# Sheet2.net
KiCad netlist of a schematic drawn in Altium Designer
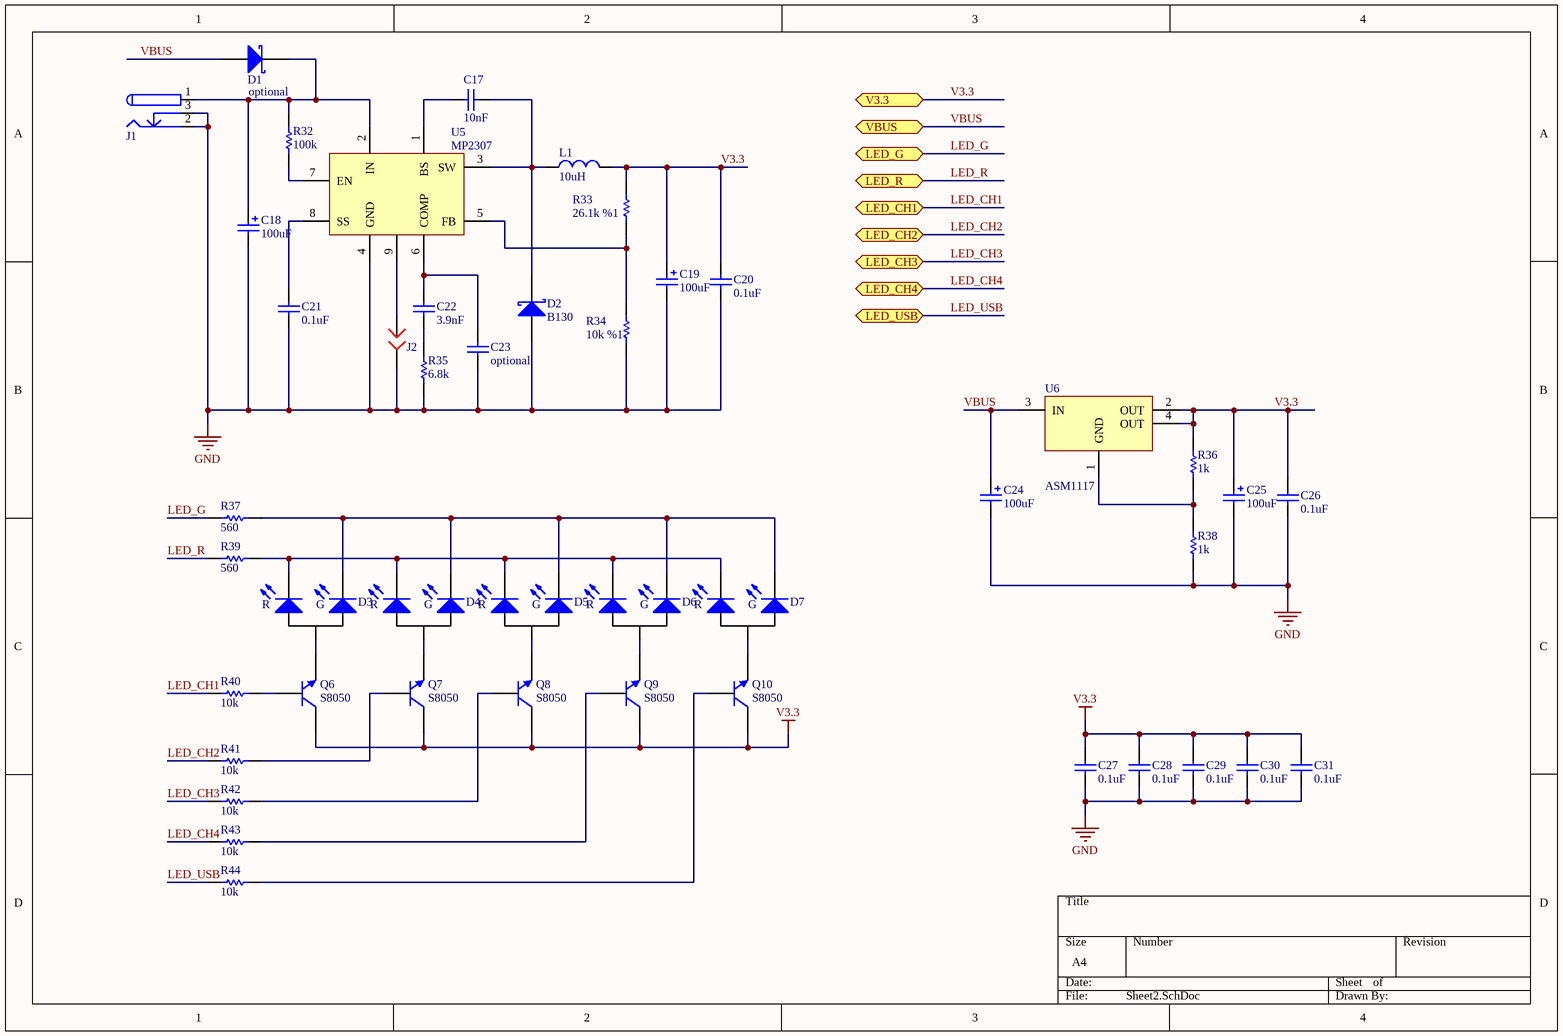
[diagram p0: Sheet2.SchDoc]

(export (version "E")
  (design (tool "Eeschema 10.0.6"))
  (components
    (comp (ref "C17")
      (value "10nF")
      (footprint "0805")
      (fields (field (name "Comment") "Cap"))
      (libsource (lib "SelfLib") (part "Cap"))
    )
    (comp (ref "C18")
      (value "100uF")
      (footprint "1206A")
      (fields (field (name "Comment") "Cap"))
      (libsource (lib "SelfLib") (part "Cap Pol"))
    )
    (comp (ref "C19")
      (value "100uF")
      (footprint "1206A")
      (fields (field (name "Comment") "Cap"))
      (libsource (lib "SelfLib") (part "Cap Pol"))
    )
    (comp (ref "C20")
      (value "0.1uF")
      (footprint "0805")
      (fields (field (name "Comment") "Cap"))
      (libsource (lib "SelfLib") (part "Cap"))
    )
    (comp (ref "C21")
      (value "0.1uF")
      (footprint "0805")
      (fields (field (name "Comment") "Cap"))
      (libsource (lib "SelfLib") (part "Cap"))
    )
    (comp (ref "C22")
      (value "3.9nF")
      (footprint "0805")
      (fields (field (name "Comment") "Cap"))
      (libsource (lib "SelfLib") (part "Cap"))
    )
    (comp (ref "C23")
      (value "optional")
      (footprint "0805")
      (fields (field (name "Comment") "Cap"))
      (libsource (lib "SelfLib") (part "Cap"))
    )
    (comp (ref "C24")
      (value "100uF")
      (footprint "0805A")
      (fields (field (name "Comment") "Cap"))
      (libsource (lib "SelfLib") (part "Cap Pol"))
    )
    (comp (ref "C25")
      (value "100uF")
      (footprint "0805A")
      (fields (field (name "Comment") "Cap"))
      (libsource (lib "SelfLib") (part "Cap Pol"))
    )
    (comp (ref "C26")
      (value "0.1uF")
      (footprint "0805")
      (fields (field (name "Comment") "Cap"))
      (libsource (lib "SelfLib") (part "Cap"))
    )
    (comp (ref "C27")
      (value "0.1uF")
      (footprint "0805")
      (fields (field (name "Comment") "Cap"))
      (libsource (lib "SelfLib") (part "Cap"))
    )
    (comp (ref "C28")
      (value "0.1uF")
      (footprint "0805")
      (fields (field (name "Comment") "Cap"))
      (libsource (lib "SelfLib") (part "Cap"))
    )
    (comp (ref "C29")
      (value "0.1uF")
      (footprint "0805")
      (fields (field (name "Comment") "Cap"))
      (libsource (lib "SelfLib") (part "Cap"))
    )
    (comp (ref "C30")
      (value "0.1uF")
      (footprint "0805")
      (fields (field (name "Comment") "Cap"))
      (libsource (lib "SelfLib") (part "Cap"))
    )
    (comp (ref "C31")
      (value "0.1uF")
      (footprint "0805")
      (fields (field (name "Comment") "Cap"))
      (libsource (lib "SelfLib") (part "Cap"))
    )
    (comp (ref "D1")
      (value "optional")
      (footprint "SMA_DO-241AC")
      (libsource (lib "SelfLib") (part "Diode 2"))
    )
    (comp (ref "D2") (value "B130") (footprint "SMA_DO-241AC") (libsource (lib "SelfLib") (part "Diode 2")))
    (comp (ref "D3") (value "LED") (footprint "LED-D") (libsource (lib "SelfLib") (part "LED2")))
    (comp (ref "D4") (value "LED") (footprint "LED-D") (libsource (lib "SelfLib") (part "LED2")))
    (comp (ref "D5") (value "LED") (footprint "LED-D") (libsource (lib "SelfLib") (part "LED2")))
    (comp (ref "D6") (value "LED") (footprint "LED-D") (libsource (lib "SelfLib") (part "LED2")))
    (comp (ref "D7") (value "LED") (footprint "LED-D") (libsource (lib "SelfLib") (part "LED2")))
    (comp (ref "J1")
      (value "PowerSocket")
      (footprint "SP_PWR")
      (description "Power Socket")
      (libsource (lib "SelfLib") (part "PWR"))
    )
    (comp (ref "J2") (value "Jump") (footprint "SP_JUMP") (libsource (lib "SelfLib") (part "Jump")))
    (comp (ref "L1")
      (value "10uH")
      (footprint "GD4520/4532")
      (fields (field (name "Comment") "Inductance"))
      (libsource (lib "SelfLib") (part "Inductance"))
    )
    (comp (ref "Q6") (value "S8050") (footprint "SOT-23") (libsource (lib "SelfLib") (part "S8050")))
    (comp (ref "Q7") (value "S8050") (footprint "SOT-23") (libsource (lib "SelfLib") (part "S8050")))
    (comp (ref "Q8") (value "S8050") (footprint "SOT-23") (libsource (lib "SelfLib") (part "S8050")))
    (comp (ref "Q9") (value "S8050") (footprint "SOT-23") (libsource (lib "SelfLib") (part "S8050")))
    (comp (ref "Q10") (value "S8050") (footprint "SOT-23") (libsource (lib "SelfLib") (part "S8050")))
    (comp (ref "R32")
      (value "100k")
      (footprint "0805")
      (fields (field (name "Comment") "Res"))
      (libsource (lib "SelfLib") (part "Res"))
    )
    (comp (ref "R33")
      (value "26.1k %1")
      (footprint "0805")
      (fields (field (name "Comment") "Res"))
      (libsource (lib "SelfLib") (part "Res"))
    )
    (comp (ref "R34")
      (value "10k %1")
      (footprint "0805")
      (fields (field (name "Comment") "Res"))
      (libsource (lib "SelfLib") (part "Res"))
    )
    (comp (ref "R35")
      (value "6.8k")
      (footprint "0805")
      (fields (field (name "Comment") "Res"))
      (libsource (lib "SelfLib") (part "Res"))
    )
    (comp (ref "R36")
      (value "1k")
      (footprint "0805")
      (fields (field (name "Comment") "Res"))
      (libsource (lib "SelfLib") (part "Res"))
    )
    (comp (ref "R37")
      (value "560")
      (footprint "0805")
      (fields (field (name "Comment") "Res"))
      (libsource (lib "SelfLib") (part "Res"))
    )
    (comp (ref "R38")
      (value "1k")
      (footprint "0805")
      (fields (field (name "Comment") "Res"))
      (libsource (lib "SelfLib") (part "Res"))
    )
    (comp (ref "R39")
      (value "560")
      (footprint "0805")
      (fields (field (name "Comment") "Res"))
      (libsource (lib "SelfLib") (part "Res"))
    )
    (comp (ref "R40")
      (value "10k")
      (footprint "0805")
      (fields (field (name "Comment") "Res"))
      (libsource (lib "SelfLib") (part "Res"))
    )
    (comp (ref "R41")
      (value "10k")
      (footprint "0805")
      (fields (field (name "Comment") "Res"))
      (libsource (lib "SelfLib") (part "Res"))
    )
    (comp (ref "R42")
      (value "10k")
      (footprint "0805")
      (fields (field (name "Comment") "Res"))
      (libsource (lib "SelfLib") (part "Res"))
    )
    (comp (ref "R43")
      (value "10k")
      (footprint "0805")
      (fields (field (name "Comment") "Res"))
      (libsource (lib "SelfLib") (part "Res"))
    )
    (comp (ref "R44")
      (value "10k")
      (footprint "0805")
      (fields (field (name "Comment") "Res"))
      (libsource (lib "SelfLib") (part "Res"))
    )
    (comp (ref "U5") (value "MP2307") (footprint "SOIC8N") (libsource (lib "SelfLib") (part "MP2307")))
    (comp (ref "U6") (value "ASM1117") (footprint "SOT-223") (libsource (lib "SelfLib") (part "ASM1117")))
  )
  (nets
    (net (code "1") (name "/LED_CH1") (class "Default")
      (node (ref "R40") (pin "2") (pinfunction "2_2") (pintype "passive"))
    )
    (net (code "2") (name "/LED_CH2") (class "Default")
      (node (ref "R41") (pin "2") (pinfunction "2_2") (pintype "passive"))
    )
    (net (code "3") (name "/LED_CH3") (class "Default")
      (node (ref "R42") (pin "2") (pinfunction "2_2") (pintype "passive"))
    )
    (net (code "4") (name "/LED_CH4") (class "Default")
      (node (ref "R43") (pin "2") (pinfunction "2_2") (pintype "passive"))
    )
    (net (code "5") (name "/LED_G") (class "Default")
      (node (ref "R37") (pin "1") (pinfunction "1_1") (pintype "passive"))
    )
    (net (code "6") (name "/LED_R") (class "Default")
      (node (ref "R39") (pin "1") (pinfunction "1_1") (pintype "passive"))
    )
    (net (code "7") (name "/LED_USB") (class "Default")
      (node (ref "R44") (pin "1") (pinfunction "1_1") (pintype "passive"))
    )
    (net (code "8") (name "/VBUS") (class "Default")
      (node (ref "C24") (pin "1") (pinfunction "1_1") (pintype "passive"))
      (node (ref "D1") (pin "1") (pinfunction "A_1") (pintype "passive"))
      (node (ref "U6") (pin "3") (pinfunction "IN_3") (pintype "passive"))
    )
    (net (code "9") (name "GND") (class "Default")
      (node (ref "C18") (pin "2") (pinfunction "2_2") (pintype "passive"))
      (node (ref "C19") (pin "2") (pinfunction "2_2") (pintype "passive"))
      (node (ref "C20") (pin "1") (pinfunction "1_1") (pintype "passive"))
      (node (ref "C21") (pin "1") (pinfunction "1_1") (pintype "passive"))
      (node (ref "C23") (pin "1") (pinfunction "1_1") (pintype "passive"))
      (node (ref "C24") (pin "2") (pinfunction "2_2") (pintype "passive"))
      (node (ref "C25") (pin "2") (pinfunction "2_2") (pintype "passive"))
      (node (ref "C26") (pin "1") (pinfunction "1_1") (pintype "passive"))
      (node (ref "C27") (pin "1") (pinfunction "1_1") (pintype "passive"))
      (node (ref "C28") (pin "1") (pinfunction "1_1") (pintype "passive"))
      (node (ref "C29") (pin "1") (pinfunction "1_1") (pintype "passive"))
      (node (ref "C30") (pin "1") (pinfunction "1_1") (pintype "passive"))
      (node (ref "C31") (pin "1") (pinfunction "1_1") (pintype "passive"))
      (node (ref "D2") (pin "1") (pinfunction "A_1") (pintype "passive"))
      (node (ref "J1") (pin "2") (pinfunction "K_2") (pintype "passive"))
      (node (ref "J1") (pin "3") (pinfunction "K_NC_3") (pintype "passive"))
      (node (ref "J2") (pin "1") (pinfunction "C1_1") (pintype "passive"))
      (node (ref "R34") (pin "1") (pinfunction "1_1") (pintype "passive"))
      (node (ref "R35") (pin "1") (pinfunction "1_1") (pintype "passive"))
      (node (ref "R38") (pin "1") (pinfunction "1_1") (pintype "passive"))
      (node (ref "U5") (pin "4") (pinfunction "GND_4") (pintype "passive"))
    )
    (net (code "10") (name "Net-(C22-Pad1)") (class "Default")
      (node (ref "C22") (pin "1") (pinfunction "1_1") (pintype "passive"))
      (node (ref "R35") (pin "2") (pinfunction "2_2") (pintype "passive"))
    )
    (net (code "11") (name "Net-(D1-K)") (class "Default")
      (node (ref "C18") (pin "1") (pinfunction "1_1") (pintype "passive"))
      (node (ref "D1") (pin "2") (pinfunction "K_2") (pintype "passive"))
      (node (ref "J1") (pin "1") (pinfunction "A_1") (pintype "passive"))
      (node (ref "R32") (pin "2") (pinfunction "2_2") (pintype "passive"))
      (node (ref "U5") (pin "2") (pinfunction "IN_2") (pintype "passive"))
    )
    (net (code "12") (name "Net-(D2-K)") (class "Default")
      (node (ref "C17") (pin "2") (pinfunction "2_2") (pintype "passive"))
      (node (ref "D2") (pin "2") (pinfunction "K_2") (pintype "passive"))
      (node (ref "L1") (pin "1") (pinfunction "1_1") (pintype "passive"))
      (node (ref "U5") (pin "3") (pinfunction "SW_3") (pintype "passive"))
    )
    (net (code "13") (name "Net-(D3-A)") (class "Default")
      (node (ref "D3") (pin "2") (pinfunction "A_2") (pintype "passive"))
      (node (ref "Q6") (pin "2") (pinfunction "E_2") (pintype "passive"))
    )
    (net (code "14") (name "Net-(D3-K1)") (class "Default")
      (node (ref "D3") (pin "1") (pinfunction "K1_1") (pintype "passive"))
      (node (ref "D4") (pin "1") (pinfunction "K1_1") (pintype "passive"))
      (node (ref "D5") (pin "1") (pinfunction "K1_1") (pintype "passive"))
      (node (ref "D6") (pin "1") (pinfunction "K1_1") (pintype "passive"))
      (node (ref "D7") (pin "1") (pinfunction "K1_1") (pintype "passive"))
      (node (ref "R39") (pin "2") (pinfunction "2_2") (pintype "passive"))
    )
    (net (code "15") (name "Net-(D3-K2)") (class "Default")
      (node (ref "D3") (pin "3") (pinfunction "K2_3") (pintype "passive"))
      (node (ref "D4") (pin "3") (pinfunction "K2_3") (pintype "passive"))
      (node (ref "D5") (pin "3") (pinfunction "K2_3") (pintype "passive"))
      (node (ref "D6") (pin "3") (pinfunction "K2_3") (pintype "passive"))
      (node (ref "D7") (pin "3") (pinfunction "K2_3") (pintype "passive"))
      (node (ref "R37") (pin "2") (pinfunction "2_2") (pintype "passive"))
    )
    (net (code "16") (name "Net-(D4-A)") (class "Default")
      (node (ref "D4") (pin "2") (pinfunction "A_2") (pintype "passive"))
      (node (ref "Q7") (pin "2") (pinfunction "E_2") (pintype "passive"))
    )
    (net (code "17") (name "Net-(D5-A)") (class "Default")
      (node (ref "D5") (pin "2") (pinfunction "A_2") (pintype "passive"))
      (node (ref "Q8") (pin "2") (pinfunction "E_2") (pintype "passive"))
    )
    (net (code "18") (name "Net-(D6-A)") (class "Default")
      (node (ref "D6") (pin "2") (pinfunction "A_2") (pintype "passive"))
      (node (ref "Q9") (pin "2") (pinfunction "E_2") (pintype "passive"))
    )
    (net (code "19") (name "Net-(D7-A)") (class "Default")
      (node (ref "D7") (pin "2") (pinfunction "A_2") (pintype "passive"))
      (node (ref "Q10") (pin "2") (pinfunction "E_2") (pintype "passive"))
    )
    (net (code "20") (name "Net-(J2-C2)") (class "Default")
      (node (ref "J2") (pin "2") (pinfunction "C2_2") (pintype "passive"))
      (node (ref "U5") (pin "9") (pinfunction "ExPad_9") (pintype "passive"))
    )
    (net (code "21") (name "Net-(Q6-B)") (class "Default")
      (node (ref "Q6") (pin "1") (pinfunction "B_1") (pintype "passive"))
      (node (ref "R40") (pin "1") (pinfunction "1_1") (pintype "passive"))
    )
    (net (code "22") (name "Net-(Q7-B)") (class "Default")
      (node (ref "Q7") (pin "1") (pinfunction "B_1") (pintype "passive"))
      (node (ref "R41") (pin "1") (pinfunction "1_1") (pintype "passive"))
    )
    (net (code "23") (name "Net-(Q8-B)") (class "Default")
      (node (ref "Q8") (pin "1") (pinfunction "B_1") (pintype "passive"))
      (node (ref "R42") (pin "1") (pinfunction "1_1") (pintype "passive"))
    )
    (net (code "24") (name "Net-(Q9-B)") (class "Default")
      (node (ref "Q9") (pin "1") (pinfunction "B_1") (pintype "passive"))
      (node (ref "R43") (pin "1") (pinfunction "1_1") (pintype "passive"))
    )
    (net (code "25") (name "Net-(Q10-B)") (class "Default")
      (node (ref "Q10") (pin "1") (pinfunction "B_1") (pintype "passive"))
      (node (ref "R44") (pin "2") (pinfunction "2_2") (pintype "passive"))
    )
    (net (code "26") (name "Net-(U5-BS)") (class "Default")
      (node (ref "C17") (pin "1") (pinfunction "1_1") (pintype "passive"))
      (node (ref "U5") (pin "1") (pinfunction "BS_1") (pintype "passive"))
    )
    (net (code "27") (name "Net-(U5-COMP)") (class "Default")
      (node (ref "C22") (pin "2") (pinfunction "2_2") (pintype "passive"))
      (node (ref "C23") (pin "2") (pinfunction "2_2") (pintype "passive"))
      (node (ref "U5") (pin "6") (pinfunction "COMP_6") (pintype "passive"))
    )
    (net (code "28") (name "Net-(U5-EN)") (class "Default")
      (node (ref "R32") (pin "1") (pinfunction "1_1") (pintype "passive"))
      (node (ref "U5") (pin "7") (pinfunction "EN_7") (pintype "passive"))
    )
    (net (code "29") (name "Net-(U5-FB)") (class "Default")
      (node (ref "R33") (pin "1") (pinfunction "1_1") (pintype "passive"))
      (node (ref "R34") (pin "2") (pinfunction "2_2") (pintype "passive"))
      (node (ref "U5") (pin "5") (pinfunction "FB_5") (pintype "passive"))
    )
    (net (code "30") (name "Net-(U5-SS)") (class "Default")
      (node (ref "C21") (pin "2") (pinfunction "2_2") (pintype "passive"))
      (node (ref "U5") (pin "8") (pinfunction "SS_8") (pintype "passive"))
    )
    (net (code "31") (name "Net-(U6-GND)") (class "Default")
      (node (ref "R36") (pin "1") (pinfunction "1_1") (pintype "passive"))
      (node (ref "R38") (pin "2") (pinfunction "2_2") (pintype "passive"))
      (node (ref "U6") (pin "1") (pinfunction "GND_1") (pintype "passive"))
    )
    (net (code "32") (name "V3.3") (class "Default")
      (node (ref "C19") (pin "1") (pinfunction "1_1") (pintype "passive"))
      (node (ref "C20") (pin "2") (pinfunction "2_2") (pintype "passive"))
      (node (ref "C25") (pin "1") (pinfunction "1_1") (pintype "passive"))
      (node (ref "C26") (pin "2") (pinfunction "2_2") (pintype "passive"))
      (node (ref "C27") (pin "2") (pinfunction "2_2") (pintype "passive"))
      (node (ref "C28") (pin "2") (pinfunction "2_2") (pintype "passive"))
      (node (ref "C29") (pin "2") (pinfunction "2_2") (pintype "passive"))
      (node (ref "C30") (pin "2") (pinfunction "2_2") (pintype "passive"))
      (node (ref "C31") (pin "2") (pinfunction "2_2") (pintype "passive"))
      (node (ref "L1") (pin "2") (pinfunction "2_2") (pintype "passive"))
      (node (ref "Q10") (pin "3") (pinfunction "C_3") (pintype "passive"))
      (node (ref "Q6") (pin "3") (pinfunction "C_3") (pintype "passive"))
      (node (ref "Q7") (pin "3") (pinfunction "C_3") (pintype "passive"))
      (node (ref "Q8") (pin "3") (pinfunction "C_3") (pintype "passive"))
      (node (ref "Q9") (pin "3") (pinfunction "C_3") (pintype "passive"))
      (node (ref "R33") (pin "2") (pinfunction "2_2") (pintype "passive"))
      (node (ref "R36") (pin "2") (pinfunction "2_2") (pintype "passive"))
      (node (ref "U6") (pin "2") (pinfunction "OUT_2") (pintype "passive"))
      (node (ref "U6") (pin "4") (pinfunction "OUT_4") (pintype "passive"))
    )
  )
)
